# usb_ethernet.net
KiCad netlist of a schematic drawn in Altium Designer
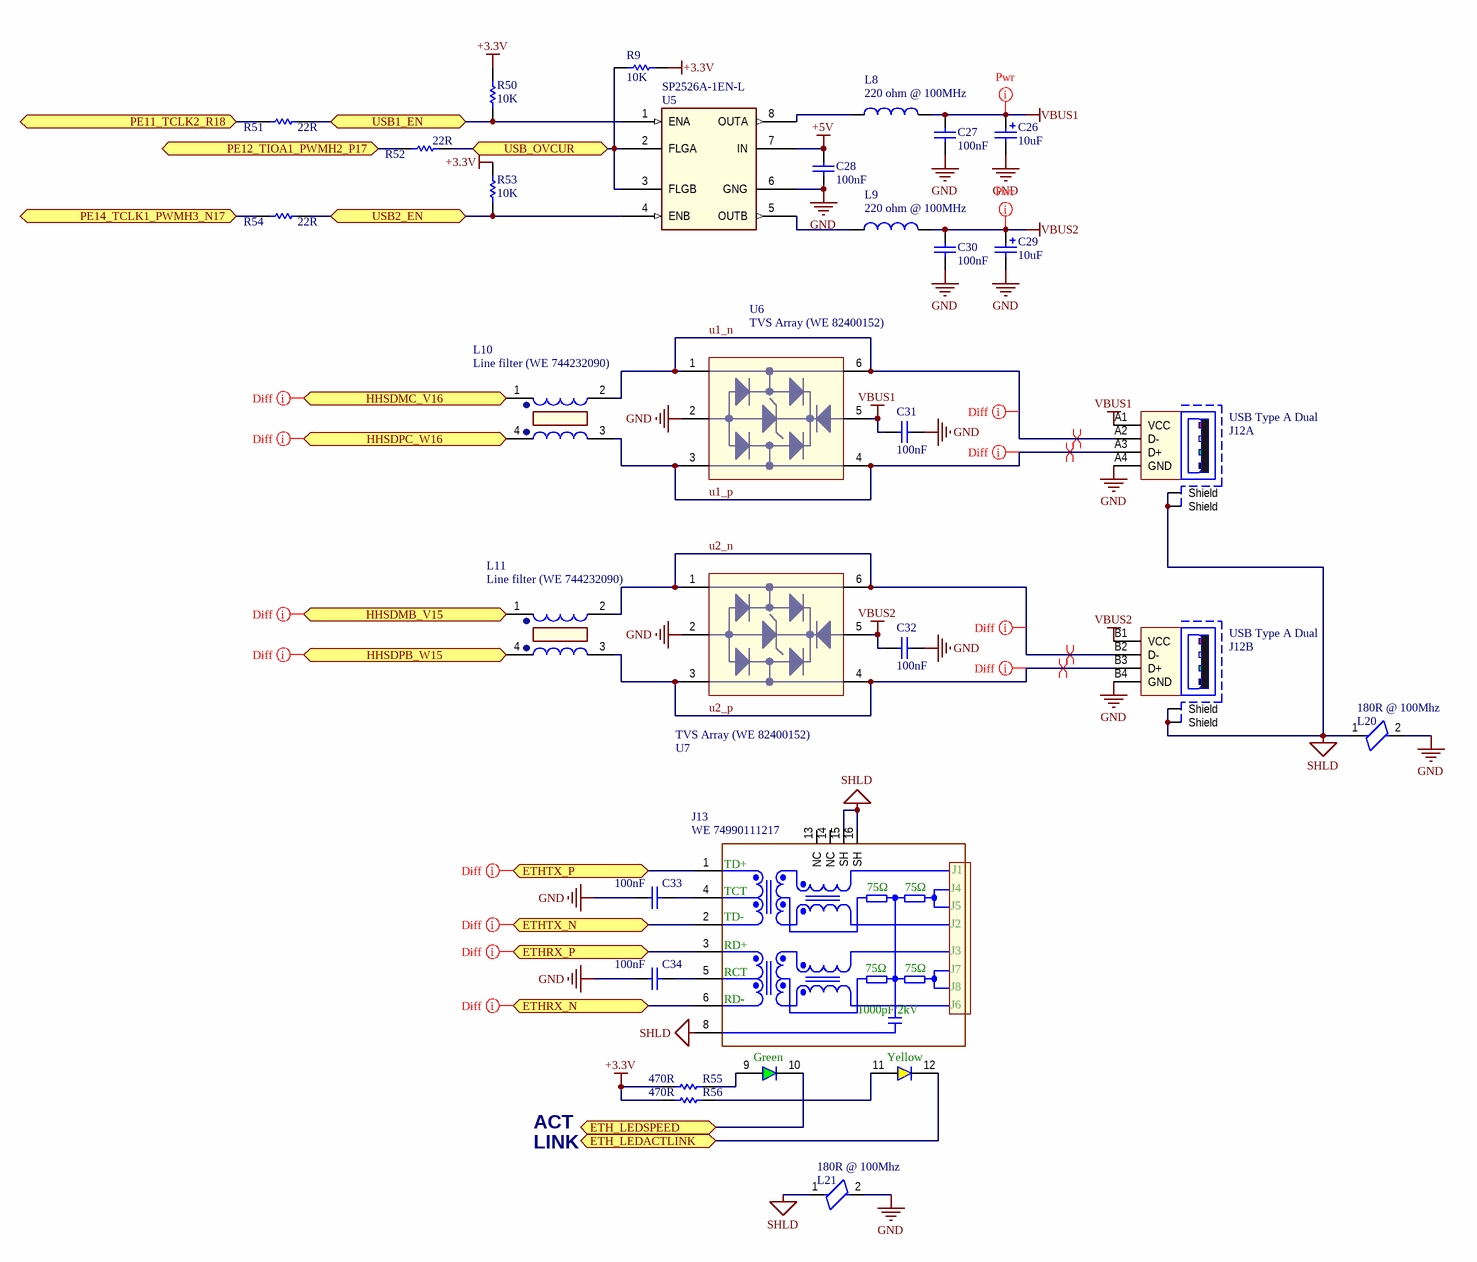
[diagram p0: usb_ethernet.SchDoc]

(export (version "E")
  (design (tool "Eeschema 10.0.6"))
  (components
    (comp (ref "C26")
      (value "10uF")
      (footprint "1206_[3216]")
      (description "Ceramic X5R 25V")
      (fields (field (name "PUBLISHER") "Altium Limited"))
      (libsource (lib "DEVELER_Library") (part "Cap Pol1"))
    )
    (comp (ref "C27")
      (value "100nF")
      (footprint "0603_[1608]")
      (description "Ceramic X7R 50V")
      (fields (field (name "PUBLISHER") "Altium Limited"))
      (libsource (lib "Miscellaneous Devices") (part "Cap"))
    )
    (comp (ref "C28")
      (value "100nF")
      (footprint "0603_[1608]")
      (description "Ceramic X7R 50V")
      (fields (field (name "PUBLISHER") "Altium Limited"))
      (libsource (lib "Miscellaneous Devices") (part "Cap"))
    )
    (comp (ref "C29")
      (value "10uF")
      (footprint "1206_[3216]")
      (description "Ceramic X5R 25V")
      (fields (field (name "PUBLISHER") "Altium Limited"))
      (libsource (lib "DEVELER_Library") (part "Cap Pol1"))
    )
    (comp (ref "C30")
      (value "100nF")
      (footprint "0603_[1608]")
      (description "Ceramic X7R 50V")
      (fields (field (name "PUBLISHER") "Altium Limited"))
      (libsource (lib "Miscellaneous Devices") (part "Cap"))
    )
    (comp (ref "C31")
      (value "100nF")
      (footprint "0603_[1608]")
      (description "Ceramic X7R 50V")
      (fields (field (name "PUBLISHER") "Altium Limited"))
      (libsource (lib "Miscellaneous Devices") (part "Cap"))
    )
    (comp (ref "C32")
      (value "100nF")
      (footprint "0603_[1608]")
      (description "Ceramic X7R 50V")
      (fields (field (name "PUBLISHER") "Altium Limited"))
      (libsource (lib "Miscellaneous Devices") (part "Cap"))
    )
    (comp (ref "C33")
      (value "100nF")
      (footprint "0603_[1608]")
      (description "Ceramic X7R 50V")
      (fields (field (name "PUBLISHER") "Altium Limited"))
      (libsource (lib "project42_lib") (part "Cap"))
    )
    (comp (ref "C34")
      (value "100nF")
      (footprint "0603_[1608]")
      (description "Ceramic X7R 50V")
      (fields (field (name "PUBLISHER") "Altium Limited"))
      (libsource (lib "project42_lib") (part "Cap"))
    )
    (comp (ref "J12")
      (value "USB Type A Dual")
      (footprint "USB_TypeA_Double_THD")
      (description "USB Type-A Double Connector (WE  61400826021)")
      (fields
        (field (name "MANUFACTURER") "Würth Elektronik eiSos GmbH")
        (field (name "PARTNO") "61400826021")
        (field (name "CREATED BY") "Karrer Zheng")
      )
      (libsource (lib "61400826021") (part "WE-Communication Connectors 61400826021"))
    )
    (comp (ref "J13")
      (value "WE 74990111217")
      (footprint "RJ45_lan_transformer_horizontal")
      (description "Integrated RJ45 Transformer WE-RJ45LAN (WE 74990111217)")
      (fields
        (field (name "PARTNO") "74980111211")
        (field (name "MANUFACTURER") "Wurth Elektronik")
        (field (name "CREATED BY") "Karrer Zheng")
        (field (name "E-MAIL") "libraries@we-online.com")
      )
      (libsource (lib "DEVELER_Library") (part "RJ45LAN-10/100BaseT"))
    )
    (comp (ref "L8")
      (value "220 ohm @ 100MHz")
      (footprint "0805_[2012]")
      (description "Ferrite Beat (WE 742792022)")
      (libsource (lib "DEVELER_Library") (part "Inductor"))
    )
    (comp (ref "L9")
      (value "220 ohm @ 100MHz")
      (footprint "0805_[2012]")
      (description "Ferrite Beat (WE 742792022)")
      (libsource (lib "DEVELER_Library") (part "Inductor"))
    )
    (comp (ref "L10")
      (value "Line filter (WE 744232090)")
      (footprint "WE-CNSW_1206")
      (description "Common mode line filter")
      (libsource (lib "DEVELER_Library") (part "Common_mode_choke"))
    )
    (comp (ref "L11")
      (value "Line filter (WE 744232090)")
      (footprint "WE-CNSW_1206")
      (description "Common mode line filter")
      (libsource (lib "DEVELER_Library") (part "Common_mode_choke"))
    )
    (comp (ref "L20")
      (value "180R @ 100Mhz")
      (footprint "0603_[1608]")
      (description "Ferrite Beat (WE 7427927218)")
      (libsource (lib "project42_lib") (part "BEAD_ FERRITE"))
    )
    (comp (ref "L21")
      (value "180R @ 100Mhz")
      (footprint "0603_[1608]")
      (description "Ferrite Beat (WE 7427927218)")
      (libsource (lib "project42_lib") (part "BEAD_ FERRITE"))
    )
    (comp (ref "R9")
      (value "10K")
      (footprint "0603_[1608]")
      (description "Resistor")
      (fields (field (name "PUBLISHER") "Altium Limited"))
      (libsource (lib "DEVELER_Library") (part "Res1"))
    )
    (comp (ref "R50")
      (value "10K")
      (footprint "0603_[1608]")
      (description "Resistor")
      (fields (field (name "PUBLISHER") "Altium Limited"))
      (libsource (lib "DEVELER_Library") (part "Res1"))
    )
    (comp (ref "R51")
      (value "22R")
      (footprint "0603_[1608]")
      (description "Resistor")
      (fields (field (name "PUBLISHER") "Altium Limited"))
      (libsource (lib "DEVELER_Library") (part "Res1"))
    )
    (comp (ref "R52")
      (value "22R")
      (footprint "0603_[1608]")
      (description "Resistor")
      (fields (field (name "PUBLISHER") "Altium Limited"))
      (libsource (lib "DEVELER_Library") (part "Res1"))
    )
    (comp (ref "R53")
      (value "10K")
      (footprint "0603_[1608]")
      (description "Resistor")
      (fields (field (name "PUBLISHER") "Altium Limited"))
      (libsource (lib "DEVELER_Library") (part "Res1"))
    )
    (comp (ref "R54")
      (value "22R")
      (footprint "0603_[1608]")
      (description "Resistor")
      (fields (field (name "PUBLISHER") "Altium Limited"))
      (libsource (lib "DEVELER_Library") (part "Res1"))
    )
    (comp (ref "R55")
      (value "470R")
      (footprint "0603_[1608]")
      (description "Resistor")
      (fields (field (name "PUBLISHER") "Altium Limited"))
      (libsource (lib "DEVELER_Library") (part "Res1"))
    )
    (comp (ref "R56")
      (value "470R")
      (footprint "0603_[1608]")
      (description "Resistor")
      (fields (field (name "PUBLISHER") "Altium Limited"))
      (libsource (lib "DEVELER_Library") (part "Res1"))
    )
    (comp (ref "U5")
      (value "SP2526A-1EN-L")
      (footprint "SOIC8")
      (description "USB Power Supply swtich HI-SIDE dual.")
      (libsource (lib "DEVELER_Library") (part "SP2526A-1EN-L"))
    )
    (comp (ref "U6")
      (value "TVS Array (WE 82400152)")
      (footprint "SOT-563")
      (libsource (lib "DEVELER_Library") (part "TVS_Diode_Array"))
    )
    (comp (ref "U7")
      (value "TVS Array (WE 82400152)")
      (footprint "SOT-563")
      (libsource (lib "DEVELER_Library") (part "TVS_Diode_Array"))
    )
  )
  (nets
    (net (code "1") (name "+3.3V") (class "Default")
      (node (ref "R50") (pin "1") (pinfunction "1_1") (pintype "passive"))
      (node (ref "R53") (pin "1") (pinfunction "1_1") (pintype "passive"))
      (node (ref "R55") (pin "2") (pinfunction "2_2") (pintype "passive"))
      (node (ref "R56") (pin "2") (pinfunction "2_2") (pintype "passive"))
      (node (ref "R9") (pin "1") (pinfunction "1_1") (pintype "passive"))
    )
    (net (code "2") (name "+5V") (class "Default")
      (node (ref "C28") (pin "1") (pinfunction "1_1") (pintype "passive"))
      (node (ref "U5") (pin "7") (pinfunction "IN_7") (pintype "power_in"))
    )
    (net (code "3") (name "/ETHRX_N") (class "Default")
      (node (ref "J13") (pin "6") (pinfunction "RD-_6") (pintype "passive"))
    )
    (net (code "4") (name "/ETHRX_P") (class "Default")
      (node (ref "J13") (pin "3") (pinfunction "RD+_3") (pintype "passive"))
    )
    (net (code "5") (name "/ETHTX_N") (class "Default")
      (node (ref "J13") (pin "2") (pinfunction "TD-_2") (pintype "passive"))
    )
    (net (code "6") (name "/ETHTX_P") (class "Default")
      (node (ref "J13") (pin "1") (pinfunction "TD+_1") (pintype "passive"))
    )
    (net (code "7") (name "/ETH_LEDACTLINK") (class "Default")
      (node (ref "J13") (pin "12") (pinfunction "Kg_12") (pintype "passive"))
    )
    (net (code "8") (name "/ETH_LEDSPEED") (class "Default")
      (node (ref "J13") (pin "10") (pinfunction "Ky_10") (pintype "passive"))
    )
    (net (code "9") (name "/HHSDMB_V15") (class "Default")
      (node (ref "L11") (pin "1") (pinfunction "1_1") (pintype "passive"))
    )
    (net (code "10") (name "/HHSDMC_V16") (class "Default")
      (node (ref "L10") (pin "1") (pinfunction "1_1") (pintype "passive"))
    )
    (net (code "11") (name "/HHSDPB_W15") (class "Default")
      (node (ref "L11") (pin "4") (pinfunction "4_4") (pintype "passive"))
    )
    (net (code "12") (name "/HHSDPC_W16") (class "Default")
      (node (ref "L10") (pin "4") (pinfunction "4_4") (pintype "passive"))
    )
    (net (code "13") (name "/PE11_TCLK2_R18") (class "Default")
      (node (ref "R51") (pin "1") (pinfunction "1_1") (pintype "passive"))
    )
    (net (code "14") (name "/PE12_TIOA1_PWMH2_P17") (class "Default")
      (node (ref "R52") (pin "1") (pinfunction "1_1") (pintype "passive"))
    )
    (net (code "15") (name "/PE14_TCLK1_PWMH3_N17") (class "Default")
      (node (ref "R54") (pin "1") (pinfunction "1_1") (pintype "passive"))
    )
    (net (code "16") (name "/USB1_EN") (class "Default")
      (node (ref "R50") (pin "2") (pinfunction "2_2") (pintype "passive"))
      (node (ref "R51") (pin "2") (pinfunction "2_2") (pintype "passive"))
      (node (ref "U5") (pin "1") (pinfunction "ENA_1") (pintype "input"))
    )
    (net (code "17") (name "/USB2_EN") (class "Default")
      (node (ref "R53") (pin "2") (pinfunction "2_2") (pintype "passive"))
      (node (ref "R54") (pin "2") (pinfunction "2_2") (pintype "passive"))
      (node (ref "U5") (pin "4") (pinfunction "ENB_4") (pintype "input"))
    )
    (net (code "18") (name "/USB_OVCUR") (class "Default")
      (node (ref "R52") (pin "2") (pinfunction "2_2") (pintype "passive"))
      (node (ref "R9") (pin "2") (pinfunction "2_2") (pintype "passive"))
      (node (ref "U5") (pin "2") (pinfunction "FLGA_2") (pintype "open_collector"))
      (node (ref "U5") (pin "3") (pinfunction "FLGB_3") (pintype "open_collector"))
    )
    (net (code "19") (name "/u1_n") (class "Default")
      (node (ref "J12") (pin "A2") (pinfunction "D-_A2") (pintype "passive"))
      (node (ref "L10") (pin "2") (pinfunction "2_2") (pintype "passive"))
      (node (ref "U6") (pin "1") (pinfunction "1_1") (pintype "passive"))
      (node (ref "U6") (pin "6") (pinfunction "6_6") (pintype "passive"))
    )
    (net (code "20") (name "/u1_p") (class "Default")
      (node (ref "J12") (pin "A3") (pinfunction "D+_A3") (pintype "passive"))
      (node (ref "L10") (pin "3") (pinfunction "3_3") (pintype "passive"))
      (node (ref "U6") (pin "3") (pinfunction "3_3") (pintype "passive"))
      (node (ref "U6") (pin "4") (pinfunction "4_4") (pintype "passive"))
    )
    (net (code "21") (name "/u2_n") (class "Default")
      (node (ref "J12") (pin "B2") (pinfunction "D-_B2") (pintype "passive"))
      (node (ref "L11") (pin "2") (pinfunction "2_2") (pintype "passive"))
      (node (ref "U7") (pin "1") (pinfunction "1_1") (pintype "passive"))
      (node (ref "U7") (pin "6") (pinfunction "6_6") (pintype "passive"))
    )
    (net (code "22") (name "/u2_p") (class "Default")
      (node (ref "J12") (pin "B3") (pinfunction "D+_B3") (pintype "passive"))
      (node (ref "L11") (pin "3") (pinfunction "3_3") (pintype "passive"))
      (node (ref "U7") (pin "3") (pinfunction "3_3") (pintype "passive"))
      (node (ref "U7") (pin "4") (pinfunction "4_4") (pintype "passive"))
    )
    (net (code "23") (name "GND") (class "Default")
      (node (ref "C26") (pin "2") (pinfunction "2_2") (pintype "passive"))
      (node (ref "C27") (pin "2") (pinfunction "2_2") (pintype "passive"))
      (node (ref "C28") (pin "2") (pinfunction "2_2") (pintype "passive"))
      (node (ref "C29") (pin "2") (pinfunction "2_2") (pintype "passive"))
      (node (ref "C30") (pin "2") (pinfunction "2_2") (pintype "passive"))
      (node (ref "C31") (pin "1") (pinfunction "1_1") (pintype "passive"))
      (node (ref "C32") (pin "1") (pinfunction "1_1") (pintype "passive"))
      (node (ref "C33") (pin "2") (pinfunction "2_2") (pintype "passive"))
      (node (ref "C34") (pin "2") (pinfunction "2_2") (pintype "passive"))
      (node (ref "J12") (pin "A4") (pinfunction "GND_A4") (pintype "passive"))
      (node (ref "J12") (pin "B4") (pinfunction "GND_B4") (pintype "passive"))
      (node (ref "L20") (pin "2") (pinfunction "2_2") (pintype "passive"))
      (node (ref "L21") (pin "2") (pinfunction "2_2") (pintype "passive"))
      (node (ref "U5") (pin "6") (pinfunction "GNG_6") (pintype "power_in"))
      (node (ref "U6") (pin "2") (pinfunction "2_2") (pintype "passive"))
      (node (ref "U7") (pin "2") (pinfunction "2_2") (pintype "passive"))
    )
    (net (code "24") (name "Net-(J13-Ag)") (class "Default")
      (node (ref "J13") (pin "11") (pinfunction "Ag_11") (pintype "passive"))
      (node (ref "R56") (pin "1") (pinfunction "1_1") (pintype "passive"))
    )
    (net (code "25") (name "Net-(J13-Ay)") (class "Default")
      (node (ref "J13") (pin "9") (pinfunction "Ay_9") (pintype "passive"))
      (node (ref "R55") (pin "1") (pinfunction "1_1") (pintype "passive"))
    )
    (net (code "26") (name "Net-(J13-RCT)") (class "Default")
      (node (ref "C34") (pin "1") (pinfunction "1_1") (pintype "passive"))
      (node (ref "J13") (pin "5") (pinfunction "RCT_5") (pintype "passive"))
    )
    (net (code "27") (name "Net-(J13-TCT)") (class "Default")
      (node (ref "C33") (pin "1") (pinfunction "1_1") (pintype "passive"))
      (node (ref "J13") (pin "4") (pinfunction "TCT_4") (pintype "passive"))
    )
    (net (code "28") (name "Net-(U5-OUTA)") (class "Default")
      (node (ref "L8") (pin "2") (pinfunction "2_2") (pintype "passive"))
      (node (ref "U5") (pin "8") (pinfunction "OUTA_8") (pintype "output"))
    )
    (net (code "29") (name "Net-(U5-OUTB)") (class "Default")
      (node (ref "L9") (pin "2") (pinfunction "2_2") (pintype "passive"))
      (node (ref "U5") (pin "5") (pinfunction "OUTB_5") (pintype "output"))
    )
    (net (code "30") (name "SHLD") (class "Default")
      (node (ref "J12") (pin "Z1") (pinfunction "Shield_Z1") (pintype "passive"))
      (node (ref "J12") (pin "Z2") (pinfunction "Shield_Z2") (pintype "passive"))
      (node (ref "J12") (pin "Z3") (pinfunction "Shield_Z3") (pintype "passive"))
      (node (ref "J12") (pin "Z4") (pinfunction "Shield_Z4") (pintype "passive"))
      (node (ref "J13") (pin "15") (pinfunction "SH_15") (pintype "passive"))
      (node (ref "J13") (pin "16") (pinfunction "SH_16") (pintype "passive"))
      (node (ref "J13") (pin "8") (pinfunction "SHLD_8") (pintype "passive"))
      (node (ref "L20") (pin "1") (pinfunction "1_1") (pintype "passive"))
      (node (ref "L21") (pin "1") (pinfunction "1_1") (pintype "passive"))
    )
    (net (code "31") (name "VBUS1") (class "Default")
      (node (ref "C26") (pin "1") (pinfunction "1_1") (pintype "passive"))
      (node (ref "C27") (pin "1") (pinfunction "1_1") (pintype "passive"))
      (node (ref "C31") (pin "2") (pinfunction "2_2") (pintype "passive"))
      (node (ref "J12") (pin "A1") (pinfunction "VCC_A1") (pintype "passive"))
      (node (ref "L8") (pin "1") (pinfunction "1_1") (pintype "passive"))
      (node (ref "U6") (pin "5") (pinfunction "5_5") (pintype "passive"))
    )
    (net (code "32") (name "VBUS2") (class "Default")
      (node (ref "C29") (pin "1") (pinfunction "1_1") (pintype "passive"))
      (node (ref "C30") (pin "1") (pinfunction "1_1") (pintype "passive"))
      (node (ref "C32") (pin "2") (pinfunction "2_2") (pintype "passive"))
      (node (ref "J12") (pin "B1") (pinfunction "VCC_B1") (pintype "passive"))
      (node (ref "L9") (pin "1") (pinfunction "1_1") (pintype "passive"))
      (node (ref "U7") (pin "5") (pinfunction "5_5") (pintype "passive"))
    )
    (net (code "33") (name "unconnected-(J13-NC-Pad13)") (class "Default")
      (node (ref "J13") (pin "13") (pinfunction "NC_13") (pintype "passive"))
    )
    (net (code "34") (name "unconnected-(J13-NC-Pad14)") (class "Default")
      (node (ref "J13") (pin "14") (pinfunction "NC_14") (pintype "passive"))
    )
  )
)
